# RevolvingStageController.net
KiCad netlist of a schematic drawn in Altium Designer
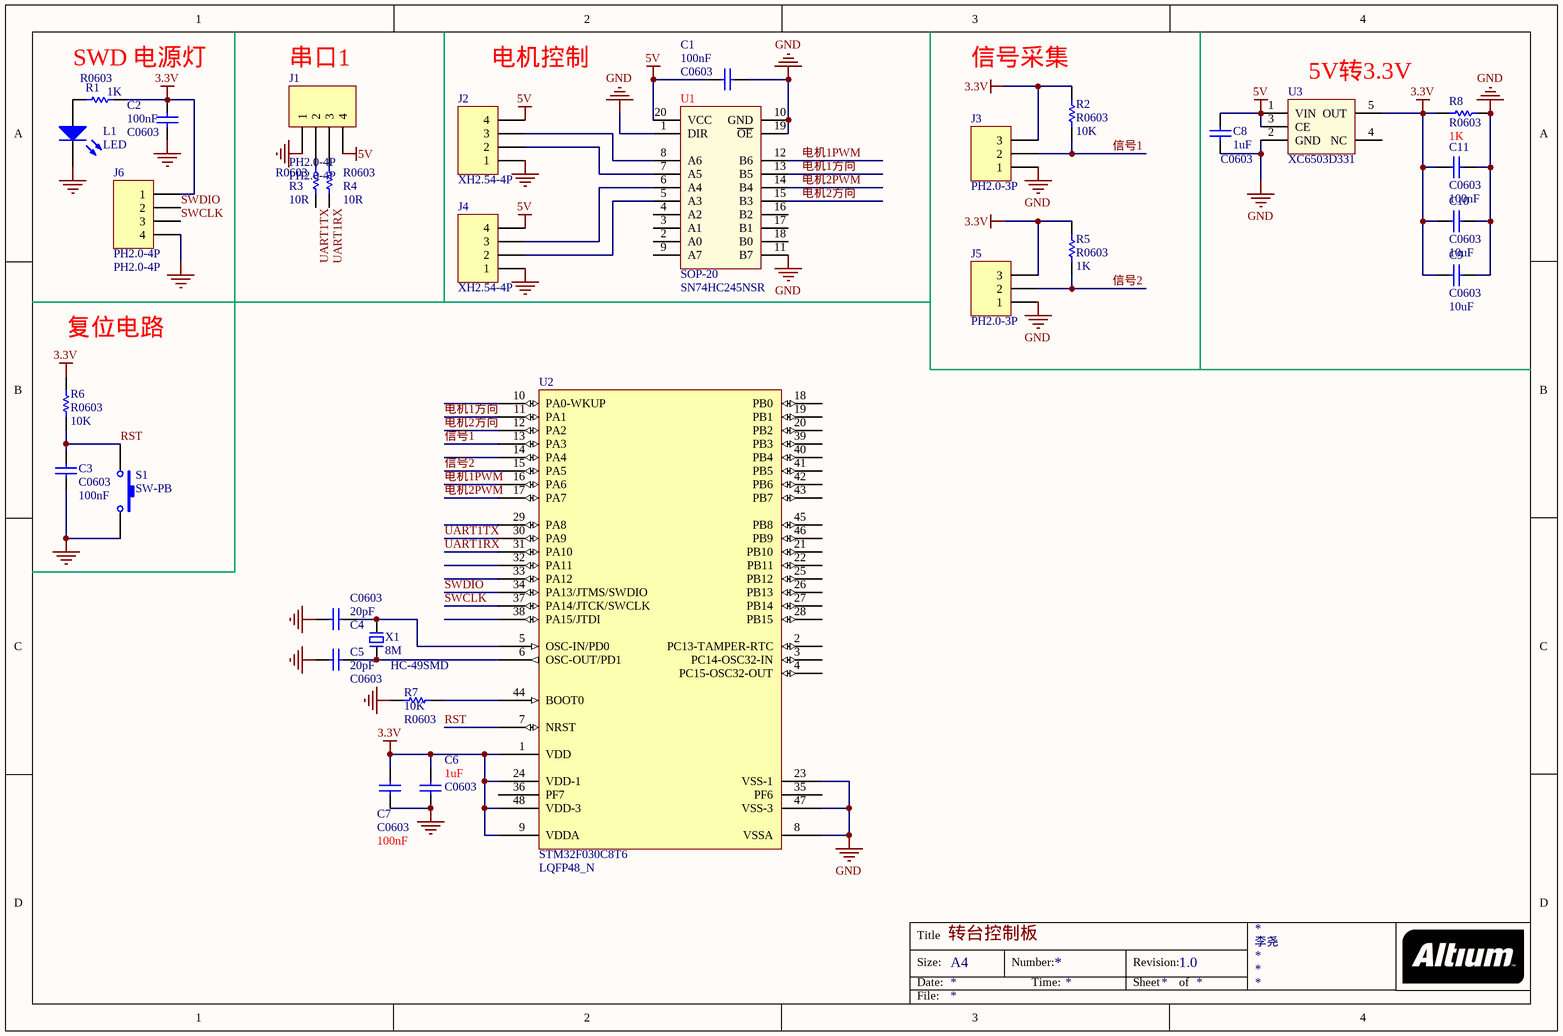
[diagram p0: RevolvingStageController.SchDoc]

(export (version "E")
  (design (tool "Eeschema 10.0.6"))
  (components
    (comp (ref "C1")
      (value "C0603")
      (footprint "C0603_M1608")
      (description "Capacitor")
      (fields (field (name "ALTIUM_VALUE") "100nF") (field (name "PUBLISHER") "Altium Limited"))
      (libsource (lib "Miscellaneous Devices") (part "Cap"))
    )
    (comp (ref "C2")
      (value "C0603")
      (footprint "C0603_M1608")
      (description "Capacitor")
      (fields (field (name "ALTIUM_VALUE") "100nF") (field (name "PUBLISHER") "Altium Limited"))
      (libsource (lib "Miscellaneous Devices") (part "Cap"))
    )
    (comp (ref "C3")
      (value "C0603")
      (footprint "C0603_M1608")
      (description "Capacitor")
      (fields (field (name "ALTIUM_VALUE") "100nF") (field (name "PUBLISHER") "Altium Limited"))
      (libsource (lib "Miscellaneous Devices") (part "Cap"))
    )
    (comp (ref "C4")
      (value "C0603")
      (footprint "C0603_M1608")
      (description "Capacitor")
      (fields (field (name "ALTIUM_VALUE") "20pF") (field (name "PUBLISHER") "Altium Limited"))
      (libsource (lib "Miscellaneous Devices") (part "Cap"))
    )
    (comp (ref "C5")
      (value "C0603")
      (footprint "C0603_M1608")
      (description "Capacitor")
      (fields (field (name "ALTIUM_VALUE") "20pF") (field (name "PUBLISHER") "Altium Limited"))
      (libsource (lib "Miscellaneous Devices") (part "Cap"))
    )
    (comp (ref "C6")
      (value "C0603")
      (footprint "C0603_M1608")
      (description "Capacitor")
      (fields (field (name "ALTIUM_VALUE") "1uF") (field (name "PUBLISHER") "Altium Limited"))
      (libsource (lib "Miscellaneous Devices") (part "Cap"))
    )
    (comp (ref "C7")
      (value "C0603")
      (footprint "C0603_M1608")
      (description "Capacitor")
      (fields (field (name "ALTIUM_VALUE") "100nF") (field (name "PUBLISHER") "Altium Limited"))
      (libsource (lib "Miscellaneous Devices") (part "Cap"))
    )
    (comp (ref "C8")
      (value "C0603")
      (footprint "C0603_M1608")
      (description "Capacitor")
      (fields (field (name "ALTIUM_VALUE") "1uF") (field (name "PUBLISHER") "Altium Limited"))
      (libsource (lib "Miscellaneous Devices") (part "Cap"))
    )
    (comp (ref "C9")
      (value "C0603")
      (footprint "C0603_M1608")
      (description "Capacitor")
      (fields (field (name "ALTIUM_VALUE") "10uF") (field (name "PUBLISHER") "Altium Limited"))
      (libsource (lib "Miscellaneous Devices") (part "Cap"))
    )
    (comp (ref "C10")
      (value "C0603")
      (footprint "C0603_M1608")
      (description "Capacitor")
      (fields (field (name "ALTIUM_VALUE") "10uF") (field (name "PUBLISHER") "Altium Limited"))
      (libsource (lib "Miscellaneous Devices") (part "Cap"))
    )
    (comp (ref "C11")
      (value "C0603")
      (footprint "C0603_M1608")
      (description "Capacitor")
      (fields (field (name "ALTIUM_VALUE") "100nF") (field (name "PUBLISHER") "Altium Limited"))
      (libsource (lib "Miscellaneous Devices") (part "Cap"))
    )
    (comp (ref "J1")
      (value "PH2.0-4P")
      (footprint "PH2.0-4P")
      (description "Header, 4-Pin")
      (fields (field (name "ALTIUM_VALUE") "PH2.0-4P") (field (name "PUBLISHER") "Altium Limited"))
      (libsource (lib "") (part "Header 4_1"))
    )
    (comp (ref "J2")
      (value "XH2.54-4P")
      (footprint "XH2.54-4")
      (description "Header, 4-Pin")
      (fields (field (name "PUBLISHER") "Altium Limited"))
      (libsource (lib "Miscellaneous Connectors") (part "Header 4"))
    )
    (comp (ref "J3")
      (value "PH2.0-3P")
      (footprint "PH2.0-3P")
      (description "Header, 3-Pin")
      (fields (field (name "PUBLISHER") "Altium Limited"))
      (libsource (lib "Sparks") (part "Header 3"))
    )
    (comp (ref "J4")
      (value "XH2.54-4P")
      (footprint "XH2.54-4")
      (description "Header, 4-Pin")
      (fields (field (name "PUBLISHER") "Altium Limited"))
      (libsource (lib "Miscellaneous Connectors") (part "Header 4"))
    )
    (comp (ref "J5")
      (value "PH2.0-3P")
      (footprint "PH2.0-3P")
      (description "Header, 3-Pin")
      (fields (field (name "PUBLISHER") "Altium Limited"))
      (libsource (lib "Sparks") (part "Header 3"))
    )
    (comp (ref "J6")
      (value "PH2.0-4P")
      (footprint "PH2.0-4P")
      (description "Header, 4-Pin")
      (fields (field (name "ALTIUM_VALUE") "PH2.0-4P") (field (name "PUBLISHER") "Altium Limited"))
      (libsource (lib "") (part "Header 4_2"))
    )
    (comp (ref "L1") (value "LED") (footprint "C2012") (libsource (lib "Sparks") (part "LED")))
    (comp (ref "R1")
      (value "R0603")
      (footprint "0603")
      (description "Resistor")
      (fields (field (name "ALTIUM_VALUE") "1K") (field (name "PUBLISHER") "Altium Limited"))
      (libsource (lib "Miscellaneous Devices") (part "Res1"))
    )
    (comp (ref "R2")
      (value "R0603")
      (footprint "0603")
      (description "Resistor")
      (fields (field (name "ALTIUM_VALUE") "10K") (field (name "PUBLISHER") "Altium Limited"))
      (libsource (lib "Miscellaneous Devices") (part "Res1"))
    )
    (comp (ref "R3")
      (value "R0603")
      (footprint "0603")
      (description "Resistor")
      (fields (field (name "ALTIUM_VALUE") "10R") (field (name "PUBLISHER") "Altium Limited"))
      (libsource (lib "Miscellaneous Devices") (part "Res1"))
    )
    (comp (ref "R4")
      (value "R0603")
      (footprint "0603")
      (description "Resistor")
      (fields (field (name "ALTIUM_VALUE") "10R") (field (name "PUBLISHER") "Altium Limited"))
      (libsource (lib "Miscellaneous Devices") (part "Res1"))
    )
    (comp (ref "R5")
      (value "R0603")
      (footprint "0603")
      (description "Resistor")
      (fields (field (name "ALTIUM_VALUE") "1K") (field (name "PUBLISHER") "Altium Limited"))
      (libsource (lib "Miscellaneous Devices") (part "Res1"))
    )
    (comp (ref "R6")
      (value "R0603")
      (footprint "0603")
      (description "Resistor")
      (fields (field (name "ALTIUM_VALUE") "10K") (field (name "PUBLISHER") "Altium Limited"))
      (libsource (lib "Miscellaneous Devices") (part "Res1"))
    )
    (comp (ref "R7")
      (value "R0603")
      (footprint "0603")
      (description "Resistor")
      (fields (field (name "ALTIUM_VALUE") "10K") (field (name "PUBLISHER") "Altium Limited"))
      (libsource (lib "Miscellaneous Devices") (part "Res1"))
    )
    (comp (ref "R8")
      (value "R0603")
      (footprint "0603")
      (description "Resistor")
      (fields (field (name "ALTIUM_VALUE") "1K") (field (name "PUBLISHER") "Altium Limited"))
      (libsource (lib "Miscellaneous Devices") (part "Res1"))
    )
    (comp (ref "S1")
      (value "SW-PB")
      (footprint "SPST-2")
      (description "Switch")
      (fields (field (name "PUBLISHER") "Altium Limited"))
      (libsource (lib "Miscellaneous Devices") (part "SW-PB"))
    )
    (comp (ref "U1")
      (value "SOP-20")
      (footprint "SOP-20")
      (fields (field (name "ALTIUM_VALUE") "SN74HC245NSR"))
      (libsource (lib "SCH") (part "74HC245"))
    )
    (comp (ref "U2")
      (value "LQFP48_N")
      (footprint "LQFP48_N")
      (description "STM32 ARM-based 32-bit MCU with 64 Kbytes Flash, 48-pin LQFP, Industrial Temperature")
      (fields (field (name "ALTIUM_VALUE") "STM32F030C8T6") (field (name "PUBLISHER") "*"))
      (libsource (lib "ST Microcontroller 32-Bit STM32 SCH") (part "STM32F103C8T6"))
    )
    (comp (ref "U3")
      (value "XC6503D331")
      (footprint "SOT23-5")
      (libsource (lib "CYSchlib") (part "XC6503Dxxx"))
    )
    (comp (ref "X1")
      (value "8M")
      (footprint "HC-49SMD")
      (fields (field (name "ALTIUM_VALUE") "HC-49SMD"))
      (libsource (lib "CYSchlib") (part "XTAL"))
    )
  )
  (nets
    (net (code "1") (name "/RST") (class "Default")
      (node (ref "C3") (pin "1") (pinfunction "1_1") (pintype "passive"))
      (node (ref "R6") (pin "2") (pinfunction "2_2") (pintype "passive"))
      (node (ref "S1") (pin "1") (pinfunction "1_1") (pintype "passive"))
      (node (ref "U2") (pin "7") (pinfunction "NRST_7") (pintype "bidirectional"))
    )
    (net (code "2") (name "/SWCLK") (class "Default")
      (node (ref "J6") (pin "3") (pinfunction "3_3") (pintype "passive"))
      (node (ref "U2") (pin "37") (pinfunction "PA14/JTCK/SWCLK_37") (pintype "bidirectional"))
    )
    (net (code "3") (name "/SWDIO") (class "Default")
      (node (ref "J6") (pin "2") (pinfunction "2_2") (pintype "passive"))
      (node (ref "U2") (pin "34") (pinfunction "PA13/JTMS/SWDIO_34") (pintype "bidirectional"))
    )
    (net (code "4") (name "/UART1RX") (class "Default")
      (node (ref "R4") (pin "2") (pinfunction "2_2") (pintype "passive"))
      (node (ref "U2") (pin "31") (pinfunction "PA10_31") (pintype "bidirectional"))
    )
    (net (code "5") (name "/UART1TX") (class "Default")
      (node (ref "R3") (pin "2") (pinfunction "2_2") (pintype "passive"))
      (node (ref "U2") (pin "30") (pinfunction "PA9_30") (pintype "bidirectional"))
    )
    (net (code "6") (name "/信号1") (class "Default")
      (node (ref "J3") (pin "2") (pinfunction "2_2") (pintype "passive"))
      (node (ref "R2") (pin "2") (pinfunction "2_2") (pintype "passive"))
      (node (ref "U2") (pin "13") (pinfunction "PA3_13") (pintype "bidirectional"))
    )
    (net (code "7") (name "/信号2") (class "Default")
      (node (ref "J5") (pin "2") (pinfunction "2_2") (pintype "passive"))
      (node (ref "R5") (pin "2") (pinfunction "2_2") (pintype "passive"))
      (node (ref "U2") (pin "15") (pinfunction "PA5_15") (pintype "bidirectional"))
    )
    (net (code "8") (name "/电机1PWM") (class "Default")
      (node (ref "U1") (pin "12") (pinfunction "B6_12") (pintype "passive"))
      (node (ref "U2") (pin "16") (pinfunction "PA6_16") (pintype "bidirectional"))
    )
    (net (code "9") (name "/电机1方向") (class "Default")
      (node (ref "U1") (pin "13") (pinfunction "B5_13") (pintype "passive"))
      (node (ref "U2") (pin "11") (pinfunction "PA1_11") (pintype "bidirectional"))
    )
    (net (code "10") (name "/电机2PWM") (class "Default")
      (node (ref "U1") (pin "14") (pinfunction "B4_14") (pintype "passive"))
      (node (ref "U2") (pin "17") (pinfunction "PA7_17") (pintype "bidirectional"))
    )
    (net (code "11") (name "/电机2方向") (class "Default")
      (node (ref "U1") (pin "15") (pinfunction "B3_15") (pintype "passive"))
      (node (ref "U2") (pin "12") (pinfunction "PA2_12") (pintype "bidirectional"))
    )
    (net (code "12") (name "3.3V") (class "Default")
      (node (ref "C10") (pin "2") (pinfunction "2_2") (pintype "passive"))
      (node (ref "C11") (pin "2") (pinfunction "2_2") (pintype "passive"))
      (node (ref "C2") (pin "1") (pinfunction "1_1") (pintype "passive"))
      (node (ref "C6") (pin "1") (pinfunction "1_1") (pintype "passive"))
      (node (ref "C7") (pin "1") (pinfunction "1_1") (pintype "passive"))
      (node (ref "C9") (pin "1") (pinfunction "1_1") (pintype "passive"))
      (node (ref "J3") (pin "3") (pinfunction "3_3") (pintype "passive"))
      (node (ref "J5") (pin "3") (pinfunction "3_3") (pintype "passive"))
      (node (ref "J6") (pin "1") (pinfunction "1_1") (pintype "passive"))
      (node (ref "R1") (pin "2") (pinfunction "2_2") (pintype "passive"))
      (node (ref "R2") (pin "1") (pinfunction "1_1") (pintype "passive"))
      (node (ref "R5") (pin "1") (pinfunction "1_1") (pintype "passive"))
      (node (ref "R6") (pin "1") (pinfunction "1_1") (pintype "passive"))
      (node (ref "R8") (pin "2") (pinfunction "2_2") (pintype "passive"))
      (node (ref "U2") (pin "1") (pinfunction "VDD_1") (pintype "power_in"))
      (node (ref "U2") (pin "24") (pinfunction "VDD-1_24") (pintype "power_in"))
      (node (ref "U2") (pin "48") (pinfunction "VDD-3_48") (pintype "power_in"))
      (node (ref "U2") (pin "9") (pinfunction "VDDA_9") (pintype "power_in"))
      (node (ref "U3") (pin "5") (pinfunction "OUT_5") (pintype "passive"))
    )
    (net (code "13") (name "5V") (class "Default")
      (node (ref "C1") (pin "1") (pinfunction "1_1") (pintype "passive"))
      (node (ref "C8") (pin "2") (pinfunction "2_2") (pintype "passive"))
      (node (ref "J1") (pin "4") (pinfunction "4_4") (pintype "passive"))
      (node (ref "J2") (pin "4") (pinfunction "4_4") (pintype "passive"))
      (node (ref "J4") (pin "4") (pinfunction "4_4") (pintype "passive"))
      (node (ref "U1") (pin "20") (pinfunction "VCC_20") (pintype "passive"))
      (node (ref "U3") (pin "1") (pinfunction "VIN_1") (pintype "passive"))
      (node (ref "U3") (pin "3") (pinfunction "CE_3") (pintype "passive"))
    )
    (net (code "14") (name "GND") (class "Default")
      (node (ref "C1") (pin "2") (pinfunction "2_2") (pintype "passive"))
      (node (ref "C10") (pin "1") (pinfunction "1_1") (pintype "passive"))
      (node (ref "C11") (pin "1") (pinfunction "1_1") (pintype "passive"))
      (node (ref "C2") (pin "2") (pinfunction "2_2") (pintype "passive"))
      (node (ref "C3") (pin "2") (pinfunction "2_2") (pintype "passive"))
      (node (ref "C4") (pin "1") (pinfunction "1_1") (pintype "passive"))
      (node (ref "C5") (pin "1") (pinfunction "1_1") (pintype "passive"))
      (node (ref "C6") (pin "2") (pinfunction "2_2") (pintype "passive"))
      (node (ref "C7") (pin "2") (pinfunction "2_2") (pintype "passive"))
      (node (ref "C8") (pin "1") (pinfunction "1_1") (pintype "passive"))
      (node (ref "C9") (pin "2") (pinfunction "2_2") (pintype "passive"))
      (node (ref "J1") (pin "1") (pinfunction "1_1") (pintype "passive"))
      (node (ref "J2") (pin "1") (pinfunction "1_1") (pintype "passive"))
      (node (ref "J3") (pin "1") (pinfunction "1_1") (pintype "passive"))
      (node (ref "J4") (pin "1") (pinfunction "1_1") (pintype "passive"))
      (node (ref "J5") (pin "1") (pinfunction "1_1") (pintype "passive"))
      (node (ref "J6") (pin "4") (pinfunction "4_4") (pintype "passive"))
      (node (ref "L1") (pin "2") (pinfunction "K_2") (pintype "passive"))
      (node (ref "R7") (pin "1") (pinfunction "1_1") (pintype "passive"))
      (node (ref "R8") (pin "1") (pinfunction "1_1") (pintype "passive"))
      (node (ref "S1") (pin "2") (pinfunction "2_2") (pintype "passive"))
      (node (ref "U1") (pin "1") (pinfunction "DIR_1") (pintype "passive"))
      (node (ref "U1") (pin "10") (pinfunction "GND_10") (pintype "passive"))
      (node (ref "U1") (pin "11") (pinfunction "B7_11") (pintype "passive"))
      (node (ref "U1") (pin "19") (pinfunction "~{OE}_19") (pintype "passive"))
      (node (ref "U2") (pin "23") (pinfunction "VSS-1_23") (pintype "power_in"))
      (node (ref "U2") (pin "47") (pinfunction "VSS-3_47") (pintype "power_in"))
      (node (ref "U2") (pin "8") (pinfunction "VSSA_8") (pintype "power_in"))
      (node (ref "U3") (pin "2") (pinfunction "GND_2") (pintype "passive"))
    )
    (net (code "15") (name "Net-(J1-Pad2)") (class "Default")
      (node (ref "J1") (pin "2") (pinfunction "2_2") (pintype "passive"))
      (node (ref "R3") (pin "1") (pinfunction "1_1") (pintype "passive"))
    )
    (net (code "16") (name "Net-(J1-Pad3)") (class "Default")
      (node (ref "J1") (pin "3") (pinfunction "3_3") (pintype "passive"))
      (node (ref "R4") (pin "1") (pinfunction "1_1") (pintype "passive"))
    )
    (net (code "17") (name "Net-(L1-A)") (class "Default")
      (node (ref "L1") (pin "1") (pinfunction "A_1") (pintype "passive"))
      (node (ref "R1") (pin "1") (pinfunction "1_1") (pintype "passive"))
    )
    (net (code "18") (name "Net-(U1-A3)") (class "Default")
      (node (ref "J4") (pin "2") (pinfunction "2_2") (pintype "passive"))
      (node (ref "U1") (pin "5") (pinfunction "A3_5") (pintype "passive"))
    )
    (net (code "19") (name "Net-(U1-A4)") (class "Default")
      (node (ref "J4") (pin "3") (pinfunction "3_3") (pintype "passive"))
      (node (ref "U1") (pin "6") (pinfunction "A4_6") (pintype "passive"))
    )
    (net (code "20") (name "Net-(U1-A5)") (class "Default")
      (node (ref "J2") (pin "2") (pinfunction "2_2") (pintype "passive"))
      (node (ref "U1") (pin "7") (pinfunction "A5_7") (pintype "passive"))
    )
    (net (code "21") (name "Net-(U1-A6)") (class "Default")
      (node (ref "J2") (pin "3") (pinfunction "3_3") (pintype "passive"))
      (node (ref "U1") (pin "8") (pinfunction "A6_8") (pintype "passive"))
    )
    (net (code "22") (name "Net-(U2-BOOT0)") (class "Default")
      (node (ref "R7") (pin "2") (pinfunction "2_2") (pintype "passive"))
      (node (ref "U2") (pin "44") (pinfunction "BOOT0_44") (pintype "input"))
    )
    (net (code "23") (name "Net-(U2-OSC-IN{slash}PD0)") (class "Default")
      (node (ref "C4") (pin "2") (pinfunction "2_2") (pintype "passive"))
      (node (ref "U2") (pin "5") (pinfunction "OSC-IN/PD0_5") (pintype "input"))
      (node (ref "X1") (pin "2") (pinfunction "2_2") (pintype "passive"))
    )
    (net (code "24") (name "Net-(U2-OSC-OUT{slash}PD1)") (class "Default")
      (node (ref "C5") (pin "2") (pinfunction "2_2") (pintype "passive"))
      (node (ref "U2") (pin "6") (pinfunction "OSC-OUT/PD1_6") (pintype "output"))
      (node (ref "X1") (pin "1") (pinfunction "1_1") (pintype "passive"))
    )
    (net (code "25") (name "unconnected-(U1-A0-Pad2)") (class "Default")
      (node (ref "U1") (pin "2") (pinfunction "A0_2") (pintype "passive"))
    )
    (net (code "26") (name "unconnected-(U1-A1-Pad3)") (class "Default")
      (node (ref "U1") (pin "3") (pinfunction "A1_3") (pintype "passive"))
    )
    (net (code "27") (name "unconnected-(U1-A2-Pad4)") (class "Default")
      (node (ref "U1") (pin "4") (pinfunction "A2_4") (pintype "passive"))
    )
    (net (code "28") (name "unconnected-(U1-A7-Pad9)") (class "Default")
      (node (ref "U1") (pin "9") (pinfunction "A7_9") (pintype "passive"))
    )
    (net (code "29") (name "unconnected-(U1-B0-Pad18)") (class "Default")
      (node (ref "U1") (pin "18") (pinfunction "B0_18") (pintype "passive"))
    )
    (net (code "30") (name "unconnected-(U1-B1-Pad17)") (class "Default")
      (node (ref "U1") (pin "17") (pinfunction "B1_17") (pintype "passive"))
    )
    (net (code "31") (name "unconnected-(U1-B2-Pad16)") (class "Default")
      (node (ref "U1") (pin "16") (pinfunction "B2_16") (pintype "passive"))
    )
    (net (code "32") (name "unconnected-(U2-PA0-WKUP-Pad10)") (class "Default")
      (node (ref "U2") (pin "10") (pinfunction "PA0-WKUP_10") (pintype "bidirectional"))
    )
    (net (code "33") (name "unconnected-(U2-PA4-Pad14)") (class "Default")
      (node (ref "U2") (pin "14") (pinfunction "PA4_14") (pintype "bidirectional"))
    )
    (net (code "34") (name "unconnected-(U2-PA8-Pad29)") (class "Default")
      (node (ref "U2") (pin "29") (pinfunction "PA8_29") (pintype "bidirectional"))
    )
    (net (code "35") (name "unconnected-(U2-PA11-Pad32)") (class "Default")
      (node (ref "U2") (pin "32") (pinfunction "PA11_32") (pintype "bidirectional"))
    )
    (net (code "36") (name "unconnected-(U2-PA12-Pad33)") (class "Default")
      (node (ref "U2") (pin "33") (pinfunction "PA12_33") (pintype "bidirectional"))
    )
    (net (code "37") (name "unconnected-(U2-PA15{slash}JTDI-Pad38)") (class "Default")
      (node (ref "U2") (pin "38") (pinfunction "PA15/JTDI_38") (pintype "bidirectional"))
    )
    (net (code "38") (name "unconnected-(U2-PB0-Pad18)") (class "Default")
      (node (ref "U2") (pin "18") (pinfunction "PB0_18") (pintype "bidirectional"))
    )
    (net (code "39") (name "unconnected-(U2-PB1-Pad19)") (class "Default")
      (node (ref "U2") (pin "19") (pinfunction "PB1_19") (pintype "bidirectional"))
    )
    (net (code "40") (name "unconnected-(U2-PB2-Pad20)") (class "Default")
      (node (ref "U2") (pin "20") (pinfunction "PB2_20") (pintype "bidirectional"))
    )
    (net (code "41") (name "unconnected-(U2-PB3-Pad39)") (class "Default")
      (node (ref "U2") (pin "39") (pinfunction "PB3_39") (pintype "bidirectional"))
    )
    (net (code "42") (name "unconnected-(U2-PB4-Pad40)") (class "Default")
      (node (ref "U2") (pin "40") (pinfunction "PB4_40") (pintype "bidirectional"))
    )
    (net (code "43") (name "unconnected-(U2-PB5-Pad41)") (class "Default")
      (node (ref "U2") (pin "41") (pinfunction "PB5_41") (pintype "bidirectional"))
    )
    (net (code "44") (name "unconnected-(U2-PB6-Pad42)") (class "Default")
      (node (ref "U2") (pin "42") (pinfunction "PB6_42") (pintype "bidirectional"))
    )
    (net (code "45") (name "unconnected-(U2-PB7-Pad43)") (class "Default")
      (node (ref "U2") (pin "43") (pinfunction "PB7_43") (pintype "bidirectional"))
    )
    (net (code "46") (name "unconnected-(U2-PB8-Pad45)") (class "Default")
      (node (ref "U2") (pin "45") (pinfunction "PB8_45") (pintype "bidirectional"))
    )
    (net (code "47") (name "unconnected-(U2-PB9-Pad46)") (class "Default")
      (node (ref "U2") (pin "46") (pinfunction "PB9_46") (pintype "bidirectional"))
    )
    (net (code "48") (name "unconnected-(U2-PB10-Pad21)") (class "Default")
      (node (ref "U2") (pin "21") (pinfunction "PB10_21") (pintype "bidirectional"))
    )
    (net (code "49") (name "unconnected-(U2-PB11-Pad22)") (class "Default")
      (node (ref "U2") (pin "22") (pinfunction "PB11_22") (pintype "bidirectional"))
    )
    (net (code "50") (name "unconnected-(U2-PB12-Pad25)") (class "Default")
      (node (ref "U2") (pin "25") (pinfunction "PB12_25") (pintype "bidirectional"))
    )
    (net (code "51") (name "unconnected-(U2-PB13-Pad26)") (class "Default")
      (node (ref "U2") (pin "26") (pinfunction "PB13_26") (pintype "bidirectional"))
    )
    (net (code "52") (name "unconnected-(U2-PB14-Pad27)") (class "Default")
      (node (ref "U2") (pin "27") (pinfunction "PB14_27") (pintype "bidirectional"))
    )
    (net (code "53") (name "unconnected-(U2-PB15-Pad28)") (class "Default")
      (node (ref "U2") (pin "28") (pinfunction "PB15_28") (pintype "bidirectional"))
    )
    (net (code "54") (name "unconnected-(U2-PC13-TAMPER-RTC-Pad2)") (class "Default")
      (node (ref "U2") (pin "2") (pinfunction "PC13-TAMPER-RTC_2") (pintype "bidirectional"))
    )
    (net (code "55") (name "unconnected-(U2-PC14-OSC32-IN-Pad3)") (class "Default")
      (node (ref "U2") (pin "3") (pinfunction "PC14-OSC32-IN_3") (pintype "bidirectional"))
    )
    (net (code "56") (name "unconnected-(U2-PC15-OSC32-OUT-Pad4)") (class "Default")
      (node (ref "U2") (pin "4") (pinfunction "PC15-OSC32-OUT_4") (pintype "bidirectional"))
    )
    (net (code "57") (name "unconnected-(U2-PF6-Pad35)") (class "Default")
      (node (ref "U2") (pin "35") (pinfunction "PF6_35") (pintype "power_in"))
    )
    (net (code "58") (name "unconnected-(U2-PF7-Pad36)") (class "Default")
      (node (ref "U2") (pin "36") (pinfunction "PF7_36") (pintype "power_in"))
    )
    (net (code "59") (name "unconnected-(U3-NC-Pad4)") (class "Default")
      (node (ref "U3") (pin "4") (pinfunction "NC_4") (pintype "passive"))
    )
  )
)
